# pc.net
KiCad netlist of a schematic drawn in EAGLE
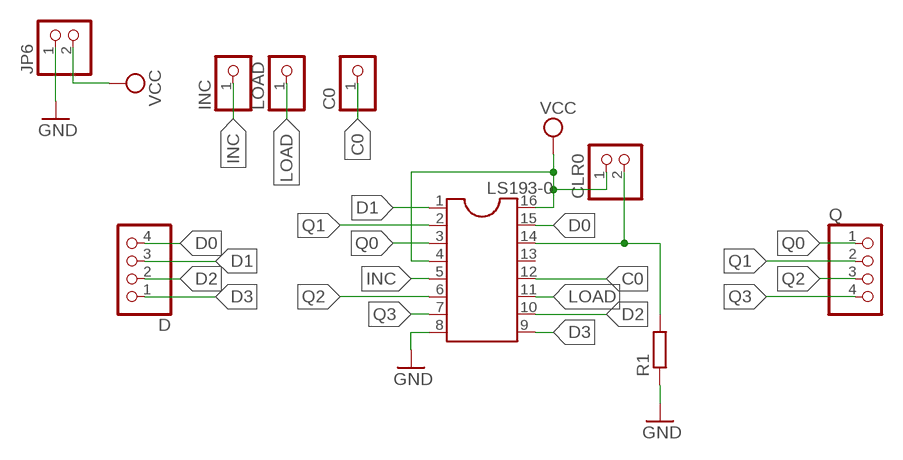
[diagram p0: schematic, sheet 1]

(export (version "E")
  (design (tool "Eeschema 10.0.6"))
  (components
    (comp (ref "C0")
      (value "PINHD-1X1")
      (footprint "eagle-import:1X01")
      (libsource (lib "eagle-import") (part "PINHD-1X1"))
    )
    (comp (ref "CLR0")
      (value "PINHD-1X2")
      (footprint "eagle-import:1X02")
      (libsource (lib "eagle-import") (part "PINHD-1X2"))
    )
    (comp (ref "D")
      (value "PINHD-1X4")
      (footprint "eagle-import:1X04")
      (libsource (lib "eagle-import") (part "PINHD-1X4"))
    )
    (comp (ref "INC")
      (value "PINHD-1X1")
      (footprint "eagle-import:1X01")
      (libsource (lib "eagle-import") (part "PINHD-1X1"))
    )
    (comp (ref "JP6")
      (value "PINHD-1X2")
      (footprint "eagle-import:1X02")
      (libsource (lib "eagle-import") (part "PINHD-1X2"))
    )
    (comp (ref "LOAD")
      (value "PINHD-1X1")
      (footprint "eagle-import:1X01")
      (libsource (lib "eagle-import") (part "PINHD-1X1"))
    )
    (comp (ref "LS193-0")
      (value "DIL16S")
      (footprint "eagle-import:SOCKET-16")
      (libsource (lib "eagle-import") (part "DIL16S"))
    )
    (comp (ref "Q")
      (value "PINHD-1X4")
      (footprint "eagle-import:1X04")
      (libsource (lib "eagle-import") (part "PINHD-1X4"))
    )
    (comp (ref "R1")
      (value "R-EU_0204/7")
      (footprint "eagle-import:0204_7")
      (libsource (lib "eagle-import") (part "R-EU_0204/7"))
    )
  )
  (nets
    (net (code "1") (name "C0") (class "Default")
      (node (ref "C0") (pin "1") (pinfunction "1_1") (pintype "passive"))
      (node (ref "LS193-0") (pin "12") (pinfunction "12_12") (pintype "passive"))
    )
    (net (code "2") (name "D0") (class "Default")
      (node (ref "D") (pin "4") (pinfunction "4_4") (pintype "passive"))
      (node (ref "LS193-0") (pin "15") (pinfunction "15_15") (pintype "passive"))
    )
    (net (code "3") (name "D1") (class "Default")
      (node (ref "D") (pin "3") (pinfunction "3_3") (pintype "passive"))
      (node (ref "LS193-0") (pin "1") (pinfunction "1_1") (pintype "passive"))
    )
    (net (code "4") (name "D2") (class "Default")
      (node (ref "D") (pin "2") (pinfunction "2_2") (pintype "passive"))
      (node (ref "LS193-0") (pin "10") (pinfunction "10_10") (pintype "passive"))
    )
    (net (code "5") (name "D3") (class "Default")
      (node (ref "D") (pin "1") (pinfunction "1_1") (pintype "passive"))
      (node (ref "LS193-0") (pin "9") (pinfunction "9_9") (pintype "passive"))
    )
    (net (code "6") (name "GND") (class "Default")
      (node (ref "JP6") (pin "1") (pinfunction "1_1") (pintype "passive"))
      (node (ref "LS193-0") (pin "8") (pinfunction "8_8") (pintype "passive"))
      (node (ref "R1") (pin "1") (pinfunction "1_1") (pintype "passive"))
    )
    (net (code "7") (name "INC") (class "Default")
      (node (ref "INC") (pin "1") (pinfunction "1_1") (pintype "passive"))
      (node (ref "LS193-0") (pin "5") (pinfunction "5_5") (pintype "passive"))
    )
    (net (code "8") (name "LOAD") (class "Default")
      (node (ref "LOAD") (pin "1") (pinfunction "1_1") (pintype "passive"))
      (node (ref "LS193-0") (pin "11") (pinfunction "11_11") (pintype "passive"))
    )
    (net (code "9") (name "Net-(CLR0-Pad2)") (class "Default")
      (node (ref "CLR0") (pin "2") (pinfunction "2_2") (pintype "passive"))
      (node (ref "LS193-0") (pin "14") (pinfunction "14_14") (pintype "passive"))
      (node (ref "R1") (pin "2") (pinfunction "2_2") (pintype "passive"))
    )
    (net (code "10") (name "Q0") (class "Default")
      (node (ref "LS193-0") (pin "3") (pinfunction "3_3") (pintype "passive"))
      (node (ref "Q") (pin "1") (pinfunction "1_1") (pintype "passive"))
    )
    (net (code "11") (name "Q1") (class "Default")
      (node (ref "LS193-0") (pin "2") (pinfunction "2_2") (pintype "passive"))
      (node (ref "Q") (pin "2") (pinfunction "2_2") (pintype "passive"))
    )
    (net (code "12") (name "Q2") (class "Default")
      (node (ref "LS193-0") (pin "6") (pinfunction "6_6") (pintype "passive"))
      (node (ref "Q") (pin "3") (pinfunction "3_3") (pintype "passive"))
    )
    (net (code "13") (name "Q3") (class "Default")
      (node (ref "LS193-0") (pin "7") (pinfunction "7_7") (pintype "passive"))
      (node (ref "Q") (pin "4") (pinfunction "4_4") (pintype "passive"))
    )
    (net (code "14") (name "VCC") (class "Default")
      (node (ref "CLR0") (pin "1") (pinfunction "1_1") (pintype "passive"))
      (node (ref "JP6") (pin "2") (pinfunction "2_2") (pintype "passive"))
      (node (ref "LS193-0") (pin "16") (pinfunction "16_16") (pintype "passive"))
      (node (ref "LS193-0") (pin "4") (pinfunction "4_4") (pintype "passive"))
    )
    (net (code "15") (name "unconnected-(LS193-0-Pad13)") (class "Default")
      (node (ref "LS193-0") (pin "13") (pinfunction "13_13") (pintype "passive"))
    )
  )
)
